# LCDTFT_CTP_FPC6P.net
KiCad netlist of a schematic drawn in Altium Designer
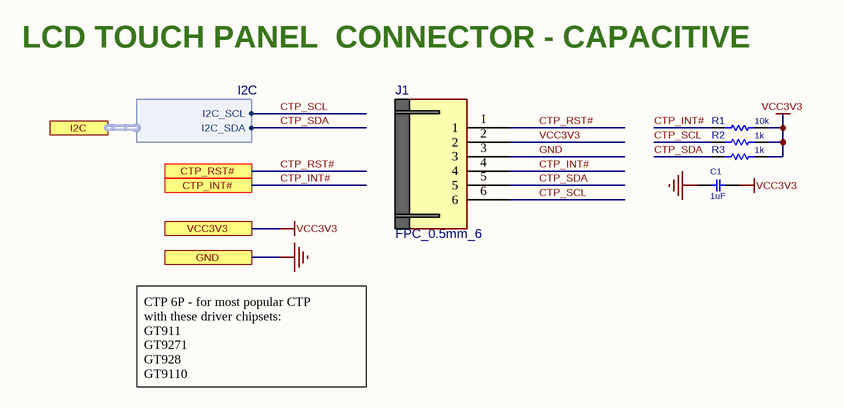
[diagram p0: LCDTFT_CTP_FPC6P.SchDoc]

(export (version "E")
  (design (tool "Eeschema 10.0.6"))
  (components
    (comp (ref "C1")
      (value "1uF")
      (footprint "C0402")
      (description "CAP, MLCC")
      (fields (field (name "MANF_P#") "CL05A105KO5NNND") (field (name "MANF") "Samsung"))
      (libsource (lib "passive_smd") (part "CAP_SMD_MLCC"))
    )
    (comp (ref "J1")
      (value "FPC_0.5mm_6")
      (footprint "FPC50_6")
      (description "CONN, FPC, 0.50mm pitch, RightAngle, Bot. Contact, Hinge type")
      (fields (field (name "MANF") "FCI") (field (name "MANF_P#") "SFV6R1STBE1HLF"))
      (libsource (lib "conn_fpc") (part "FPC50_6"))
    )
    (comp (ref "R1")
      (value "10k")
      (footprint "R0402")
      (description "RESISTOR, SMD")
      (libsource (lib "passive_res_smd") (part "RES_SMD"))
    )
    (comp (ref "R2")
      (value "1k")
      (footprint "R0402")
      (description "RESISTOR, SMD")
      (libsource (lib "passive_res_smd") (part "RES_SMD"))
    )
    (comp (ref "R3")
      (value "1k")
      (footprint "R0402")
      (description "RESISTOR, SMD")
      (libsource (lib "passive_res_smd") (part "RES_SMD"))
    )
  )
  (nets
    (net (code "2") (name "/CTP_INT#") (class "Default")
      (node (ref "J1") (pin "4") (pinfunction "4_4") (pintype "passive"))
      (node (ref "R1") (pin "1") (pinfunction "1_1") (pintype "passive"))
    )
    (net (code "3") (name "/CTP_RST#") (class "Default")
      (node (ref "J1") (pin "1") (pinfunction "1_1") (pintype "passive"))
    )
    (net (code "4") (name "/CTP_SCL") (class "Default")
      (node (ref "J1") (pin "6") (pinfunction "6_6") (pintype "passive"))
      (node (ref "R2") (pin "1") (pinfunction "1_1") (pintype "passive"))
    )
    (net (code "5") (name "/CTP_SDA") (class "Default")
      (node (ref "J1") (pin "5") (pinfunction "5_5") (pintype "passive"))
      (node (ref "R3") (pin "1") (pinfunction "1_1") (pintype "passive"))
    )
    (net (code "7") (name "GND") (class "Default")
      (node (ref "C1") (pin "2") (pinfunction "2_2") (pintype "passive"))
      (node (ref "J1") (pin "3") (pinfunction "3_3") (pintype "passive"))
    )
    (net (code "8") (name "VCC3V3") (class "Default")
      (node (ref "C1") (pin "1") (pinfunction "1_1") (pintype "passive"))
      (node (ref "J1") (pin "2") (pinfunction "2_2") (pintype "passive"))
      (node (ref "R1") (pin "2") (pinfunction "2_2") (pintype "passive"))
      (node (ref "R2") (pin "2") (pinfunction "2_2") (pintype "passive"))
      (node (ref "R3") (pin "2") (pinfunction "2_2") (pintype "passive"))
    )
  )
)
